# Overview_and_Power.net
KiCad netlist of a schematic drawn in Altium Designer
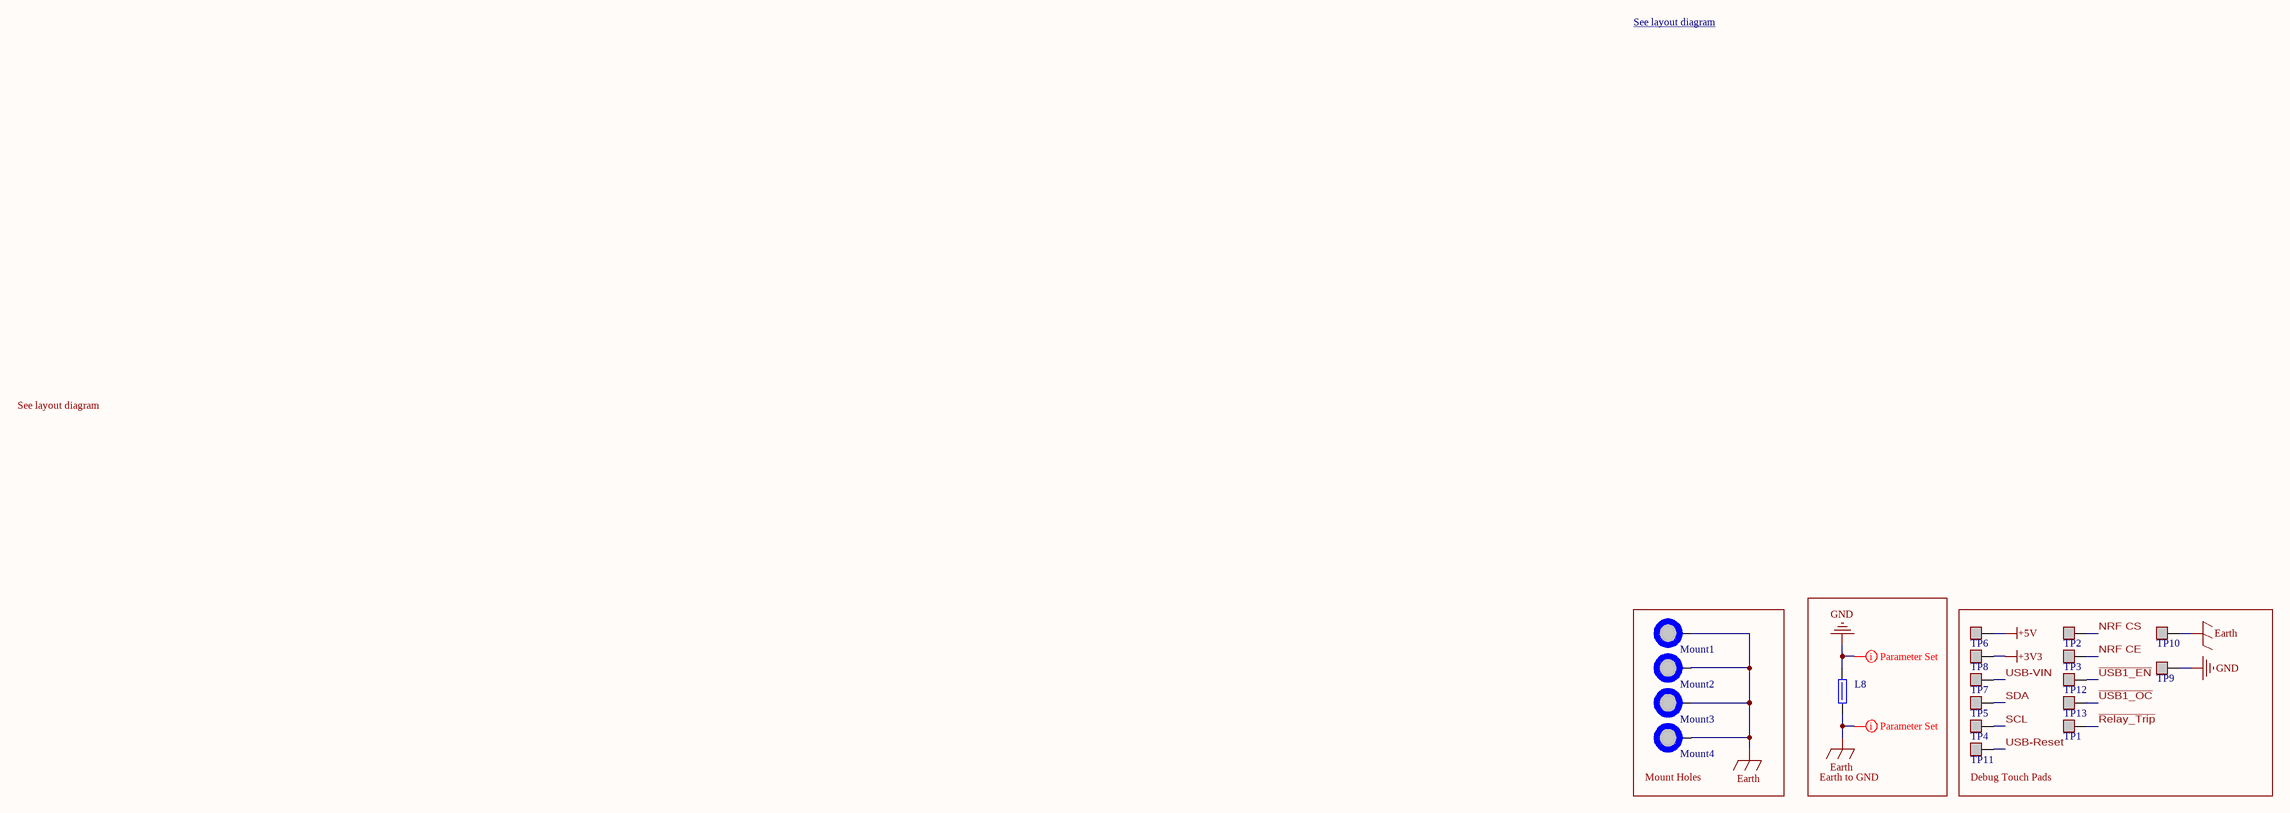
[diagram p0: Overview and Power.SchDoc]

(export (version "E")
  (design (tool "Eeschema 10.0.6"))
  (components
    (comp (ref "L8")
      (value "742792040")
      (footprint "[Ferrite] SMD Bead 0805 (2)")
      (libsource (lib "RADM Components") (part "[Ferrite] SMD Ferrite Bead (2)"))
    )
    (comp (ref "Mount1")
      (value "M3 Mount Hole")
      (footprint "[Mount] M3 Mount Hole")
      (description "Place at least 4.5mm from board edge. Plated.")
      (libsource (lib "RADM Connectors") (part "[Mount] M3 Mount Hole"))
    )
    (comp (ref "Mount2")
      (value "M3 Mount Hole")
      (footprint "[Mount] M3 Mount Hole")
      (description "Place at least 4.5mm from board edge. Plated.")
      (libsource (lib "RADM Connectors") (part "[Mount] M3 Mount Hole"))
    )
    (comp (ref "Mount3")
      (value "M3 Mount Hole")
      (footprint "[Mount] M3 Mount Hole")
      (description "Place at least 4.5mm from board edge. Plated.")
      (libsource (lib "RADM Connectors") (part "[Mount] M3 Mount Hole"))
    )
    (comp (ref "Mount4")
      (value "M3 Mount Hole")
      (footprint "[Mount] M3 Mount Hole")
      (description "Place at least 4.5mm from board edge. Plated.")
      (libsource (lib "RADM Connectors") (part "[Mount] M3 Mount Hole"))
    )
    (comp (ref "TP1")
      (value "Probe Pad")
      (footprint "[Probe] Touch Pad")
      (libsource (lib "RADM Connectors") (part "[Probe] Touch Pad"))
    )
    (comp (ref "TP2")
      (value "Probe Pad")
      (footprint "[Probe] Touch Pad")
      (libsource (lib "RADM Connectors") (part "[Probe] Touch Pad"))
    )
    (comp (ref "TP3")
      (value "Probe Pad")
      (footprint "[Probe] Touch Pad")
      (libsource (lib "RADM Connectors") (part "[Probe] Touch Pad"))
    )
    (comp (ref "TP4")
      (value "Probe Pad")
      (footprint "[Probe] Touch Pad")
      (libsource (lib "RADM Connectors") (part "[Probe] Touch Pad"))
    )
    (comp (ref "TP5")
      (value "Probe Pad")
      (footprint "[Probe] Touch Pad")
      (libsource (lib "RADM Connectors") (part "[Probe] Touch Pad"))
    )
    (comp (ref "TP6")
      (value "Probe Pad")
      (footprint "[Probe] Touch Pad")
      (libsource (lib "RADM Connectors") (part "[Probe] Touch Pad"))
    )
    (comp (ref "TP7")
      (value "Probe Pad")
      (footprint "[Probe] Touch Pad")
      (libsource (lib "RADM Connectors") (part "[Probe] Touch Pad"))
    )
    (comp (ref "TP8")
      (value "Probe Pad")
      (footprint "[Probe] Touch Pad")
      (libsource (lib "RADM Connectors") (part "[Probe] Touch Pad"))
    )
    (comp (ref "TP9")
      (value "Probe Pad")
      (footprint "[Probe] Touch Pad")
      (libsource (lib "RADM Connectors") (part "[Probe] Touch Pad"))
    )
    (comp (ref "TP10")
      (value "Probe Pad")
      (footprint "[Probe] Touch Pad")
      (libsource (lib "RADM Connectors") (part "[Probe] Touch Pad"))
    )
    (comp (ref "TP11")
      (value "Probe Pad")
      (footprint "[Probe] Touch Pad")
      (libsource (lib "RADM Connectors") (part "[Probe] Touch Pad"))
    )
    (comp (ref "TP12")
      (value "Probe Pad")
      (footprint "[Probe] Touch Pad")
      (libsource (lib "RADM Connectors") (part "[Probe] Touch Pad"))
    )
    (comp (ref "TP13")
      (value "Probe Pad")
      (footprint "[Probe] Touch Pad")
      (libsource (lib "RADM Connectors") (part "[Probe] Touch Pad"))
    )
  )
  (nets
    (net (code "1") (name "+3V3") (class "Default")
      (node (ref "TP8") (pin "1") (pinfunction "1_1") (pintype "passive"))
    )
    (net (code "2") (name "+5V") (class "Default")
      (node (ref "TP6") (pin "1") (pinfunction "1_1") (pintype "passive"))
    )
    (net (code "3") (name "/NRF CE") (class "Default")
      (node (ref "TP3") (pin "1") (pinfunction "1_1") (pintype "passive"))
    )
    (net (code "4") (name "/NRF CS") (class "Default")
      (node (ref "TP2") (pin "1") (pinfunction "1_1") (pintype "passive"))
    )
    (net (code "5") (name "/Relay_Trip") (class "Default")
      (node (ref "TP1") (pin "1") (pinfunction "1_1") (pintype "passive"))
    )
    (net (code "6") (name "/SCL") (class "Default")
      (node (ref "TP4") (pin "1") (pinfunction "1_1") (pintype "passive"))
    )
    (net (code "7") (name "/SDA") (class "Default")
      (node (ref "TP5") (pin "1") (pinfunction "1_1") (pintype "passive"))
    )
    (net (code "8") (name "/USB-Reset") (class "Default")
      (node (ref "TP11") (pin "1") (pinfunction "1_1") (pintype "passive"))
    )
    (net (code "9") (name "/USB-VIN") (class "Default")
      (node (ref "TP7") (pin "1") (pinfunction "1_1") (pintype "passive"))
    )
    (net (code "10") (name "/USB1_EN") (class "Default")
      (node (ref "TP12") (pin "1") (pinfunction "1_1") (pintype "passive"))
    )
    (net (code "11") (name "/USB1_OC") (class "Default")
      (node (ref "TP13") (pin "1") (pinfunction "1_1") (pintype "passive"))
    )
    (net (code "12") (name "Earth") (class "Default")
      (node (ref "L8") (pin "1") (pinfunction "1_1") (pintype "passive"))
      (node (ref "Mount1") (pin "1") (pintype "power_in"))
      (node (ref "Mount2") (pin "1") (pintype "power_in"))
      (node (ref "Mount3") (pin "1") (pintype "power_in"))
      (node (ref "Mount4") (pin "1") (pintype "power_in"))
      (node (ref "TP10") (pin "1") (pinfunction "1_1") (pintype "passive"))
    )
    (net (code "13") (name "GND") (class "Default")
      (node (ref "L8") (pin "2") (pinfunction "2_2") (pintype "passive"))
      (node (ref "TP9") (pin "1") (pinfunction "1_1") (pintype "passive"))
    )
  )
)
